# Battery_Charger.net
KiCad netlist of a schematic drawn in Altium Designer
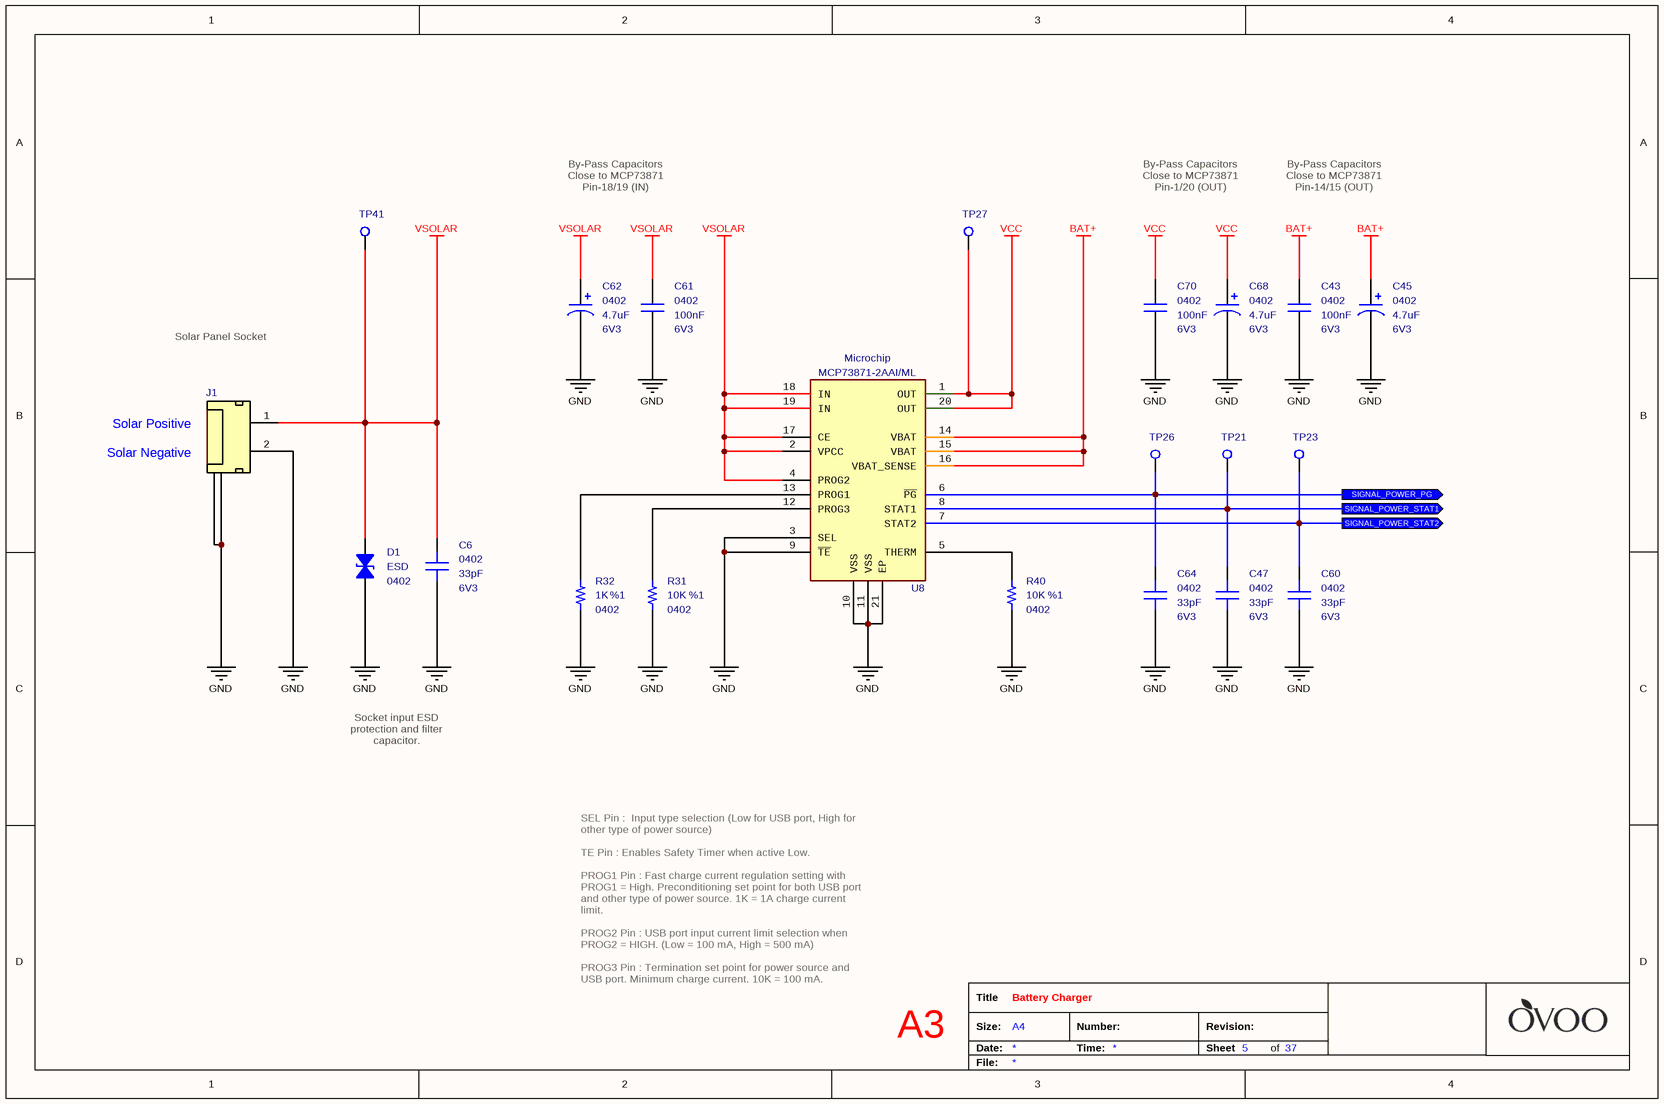
[diagram p0: Battery Charger.SchDoc]

(export (version "E")
  (design (tool "Eeschema 10.0.6"))
  (components
    (comp (ref "C6")
      (value "33pF")
      (footprint "CAPACITOR_0402")
      (description "Capacitor - 33pF [0402] (Ceramic)")
      (fields
        (field (name "MANUFACTURER_PART_NUMBER") "C0402C330J9RACAUTO")
        (field (name "MOUSER_PART_NUMBER") "80-C0402C330J9RAUTO")
        (field (name "CASE") "0402")
        (field (name "VOLTAGE") "6V3")
      )
      (libsource (lib "Ovoo_Schematic") (part "Capacitor - 33pF [0402-6V3]"))
    )
    (comp (ref "C43")
      (value "100nF")
      (footprint "CAPACITOR_0402")
      (description "Capacitor - 100nF [0402-6V3] (Ceramic)")
      (fields
        (field (name "MANUFACTURER_PART_NUMBER") "04026D104KAT4A")
        (field (name "MOUSER_PART_NUMBER") "581-04026D104KAT4A")
        (field (name "CASE") "0402")
        (field (name "VOLTAGE") "6V3")
      )
      (libsource (lib "Ovoo_Schematic") (part "Capacitor - 100nF [0402-6V3]"))
    )
    (comp (ref "C45")
      (value "4.7uF")
      (footprint "CAPACITOR_0402")
      (description "Capacitor - 4.7uF [0402] (Ceramic)")
      (fields
        (field (name "MANUFACTURER_PART_NUMBER") "C0402C475M9PACTU")
        (field (name "MOUSER_PART_NUMBER") "80-C0402C475M9P")
        (field (name "CASE") "0402")
        (field (name "VOLTAGE") "6V3")
      )
      (libsource (lib "Ovoo_Schematic") (part "Capacitor - 4.7uF [0402-6V3)"))
    )
    (comp (ref "C47")
      (value "33pF")
      (footprint "CAPACITOR_0402")
      (description "Capacitor - 33pF [0402] (Ceramic)")
      (fields
        (field (name "MANUFACTURER_PART_NUMBER") "C0402C330J9RACAUTO")
        (field (name "MOUSER_PART_NUMBER") "80-C0402C330J9RAUTO")
        (field (name "CASE") "0402")
        (field (name "VOLTAGE") "6V3")
      )
      (libsource (lib "Ovoo_Schematic") (part "Capacitor - 33pF [0402-6V3]"))
    )
    (comp (ref "C60")
      (value "33pF")
      (footprint "CAPACITOR_0402")
      (description "Capacitor - 33pF [0402] (Ceramic)")
      (fields
        (field (name "MANUFACTURER_PART_NUMBER") "C0402C330J9RACAUTO")
        (field (name "MOUSER_PART_NUMBER") "80-C0402C330J9RAUTO")
        (field (name "CASE") "0402")
        (field (name "VOLTAGE") "6V3")
      )
      (libsource (lib "Ovoo_Schematic") (part "Capacitor - 33pF [0402-6V3]"))
    )
    (comp (ref "C61")
      (value "100nF")
      (footprint "CAPACITOR_0402")
      (description "Capacitor - 100nF [0402-6V3] (Ceramic)")
      (fields
        (field (name "MANUFACTURER_PART_NUMBER") "04026D104KAT4A")
        (field (name "MOUSER_PART_NUMBER") "581-04026D104KAT4A")
        (field (name "CASE") "0402")
        (field (name "VOLTAGE") "6V3")
      )
      (libsource (lib "Ovoo_Schematic") (part "Capacitor - 100nF [0402-6V3]"))
    )
    (comp (ref "C62")
      (value "4.7uF")
      (footprint "CAPACITOR_0402")
      (description "Capacitor - 4.7uF [0402] (Ceramic)")
      (fields
        (field (name "MANUFACTURER_PART_NUMBER") "C0402C475M9PACTU")
        (field (name "MOUSER_PART_NUMBER") "80-C0402C475M9P")
        (field (name "CASE") "0402")
        (field (name "VOLTAGE") "6V3")
      )
      (libsource (lib "Ovoo_Schematic") (part "Capacitor - 4.7uF [0402-6V3)"))
    )
    (comp (ref "C64")
      (value "33pF")
      (footprint "CAPACITOR_0402")
      (description "Capacitor - 33pF [0402] (Ceramic)")
      (fields
        (field (name "MANUFACTURER_PART_NUMBER") "C0402C330J9RACAUTO")
        (field (name "MOUSER_PART_NUMBER") "80-C0402C330J9RAUTO")
        (field (name "CASE") "0402")
        (field (name "VOLTAGE") "6V3")
      )
      (libsource (lib "Ovoo_Schematic") (part "Capacitor - 33pF [0402-6V3]"))
    )
    (comp (ref "C68")
      (value "4.7uF")
      (footprint "CAPACITOR_0402")
      (description "Capacitor - 4.7uF [0402] (Ceramic)")
      (fields
        (field (name "MANUFACTURER_PART_NUMBER") "C0402C475M9PACTU")
        (field (name "MOUSER_PART_NUMBER") "80-C0402C475M9P")
        (field (name "CASE") "0402")
        (field (name "VOLTAGE") "6V3")
      )
      (libsource (lib "Ovoo_Schematic") (part "Capacitor - 4.7uF [0402-6V3)"))
    )
    (comp (ref "C70")
      (value "100nF")
      (footprint "CAPACITOR_0402")
      (description "Capacitor - 100nF [0402-6V3] (Ceramic)")
      (fields
        (field (name "MANUFACTURER_PART_NUMBER") "04026D104KAT4A")
        (field (name "MOUSER_PART_NUMBER") "581-04026D104KAT4A")
        (field (name "CASE") "0402")
        (field (name "VOLTAGE") "6V3")
      )
      (libsource (lib "Ovoo_Schematic") (part "Capacitor - 100nF [0402-6V3]"))
    )
    (comp (ref "D1")
      (value "ESD Suppressors")
      (footprint "ESD_0402")
      (description "TVS Diode (Bi-directional)")
      (fields
        (field (name "MANUFACTURER_PART_NUMBER") "0402ESDA-MLP1")
        (field (name "MOUSER_PART_NUMBER") "504-0402ESDA-MLP1")
        (field (name "CASE") "0402")
      )
      (libsource (lib "Ovoo_Schematic") (part "Diode - ESD Protection"))
    )
    (comp (ref "J1")
      (value "Solar Power Socket")
      (footprint "Connector_Tunic 2P - H")
      (description "Mini Tunic Connector with 2P")
      (fields
        (field (name "MANUFACTURER_PART_NUMBER") "53261-0271")
        (field (name "MOUSER_PART_NUMBER") "538-53261-0271")
      )
      (libsource (lib "Ovoo_Schematic") (part "Connector - Mini Tunic 2P (1.25)"))
    )
    (comp (ref "R31")
      (value "10K")
      (footprint "RESISTOR_0402")
      (description "Thick Film Resistors - SMD 1/16 W 10 Kohms 1%")
      (fields
        (field (name "MANUFACTURER_PART_NUMBER") "CRCW040210K0FKED")
        (field (name "MOUSER_PART_NUMBER") "71-CRCW0402-10K-E3")
        (field (name "TOLERANCE") "%1")
        (field (name "CASE") "0402")
      )
      (libsource (lib "Ovoo_Schematic") (part "Resistor - 10K"))
    )
    (comp (ref "R32")
      (value "1K")
      (footprint "RESISTOR_0402")
      (description "Thick Film Resistors - SMD 1/16 W 1.0 Kohms 1%")
      (fields
        (field (name "MANUFACTURER_PART_NUMBER") "CRCW04021K00FKED")
        (field (name "MOUSER_PART_NUMBER") "71-CRCW0402-1.0K-E3")
        (field (name "CASE") "0402")
        (field (name "TOLERANCE") "%1")
      )
      (libsource (lib "Ovoo_Schematic") (part "Resistor - 1K"))
    )
    (comp (ref "R40")
      (value "10K")
      (footprint "RESISTOR_0402")
      (description "Thick Film Resistors - SMD 1/16 W 10 Kohms 1%")
      (fields
        (field (name "MANUFACTURER_PART_NUMBER") "CRCW040210K0FKED")
        (field (name "MOUSER_PART_NUMBER") "71-CRCW0402-10K-E3")
        (field (name "TOLERANCE") "%1")
        (field (name "CASE") "0402")
      )
      (libsource (lib "Ovoo_Schematic") (part "Resistor - 10K"))
    )
    (comp (ref "TP21")
      (value "PCB - Test Point")
      (footprint "Test_Pad - Hole")
      (description "Test Point")
      (libsource (lib "Ovoo_Schematic") (part "PCB - Test Point"))
    )
    (comp (ref "TP23")
      (value "PCB - Test Point")
      (footprint "Test_Pad - Hole")
      (description "Test Point")
      (libsource (lib "Ovoo_Schematic") (part "PCB - Test Point"))
    )
    (comp (ref "TP26")
      (value "PCB - Test Point")
      (footprint "Test_Pad - Hole")
      (description "Test Point")
      (libsource (lib "Ovoo_Schematic") (part "PCB - Test Point"))
    )
    (comp (ref "TP27")
      (value "PCB - Test Point")
      (footprint "Test_Pad - Hole")
      (description "Test Point")
      (libsource (lib "Ovoo_Schematic") (part "PCB - Test Point"))
    )
    (comp (ref "TP41")
      (value "PCB - Test Point")
      (footprint "Test_Pad - Hole")
      (description "Test Point")
      (libsource (lib "Ovoo_Schematic") (part "PCB - Test Point"))
    )
    (comp (ref "U8")
      (value "Battery Charger")
      (footprint "QFN20")
      (description "Battery Management USB/AC Battery Charger")
      (fields
        (field (name "MANUFACTURER_NAME") "Microchip")
        (field (name "MANUFACTURER_PART_NUMBER") "MCP73871-2AAI/ML")
        (field (name "MOUSER_PART_NUMBER") "579-MCP73871-2AAI/ML")
      )
      (libsource (lib "Ovoo_Schematic") (part "IC - MCP73871"))
    )
  )
  (nets
    (net (code "1") (name "/SIGNAL_POWER_PG") (class "Default")
      (node (ref "C64") (pin "1") (pinfunction "1_1") (pintype "passive"))
      (node (ref "TP26") (pin "1") (pinfunction "1_1") (pintype "passive"))
      (node (ref "U8") (pin "6") (pinfunction "~{PG}_6") (pintype "open_collector"))
    )
    (net (code "2") (name "/SIGNAL_POWER_STAT1") (class "Default")
      (node (ref "C47") (pin "1") (pinfunction "1_1") (pintype "passive"))
      (node (ref "TP21") (pin "1") (pinfunction "1_1") (pintype "passive"))
      (node (ref "U8") (pin "8") (pinfunction "STAT1_8") (pintype "open_collector"))
    )
    (net (code "3") (name "/SIGNAL_POWER_STAT2") (class "Default")
      (node (ref "C60") (pin "1") (pinfunction "1_1") (pintype "passive"))
      (node (ref "TP23") (pin "1") (pinfunction "1_1") (pintype "passive"))
      (node (ref "U8") (pin "7") (pinfunction "STAT2_7") (pintype "open_collector"))
    )
    (net (code "4") (name "BAT+") (class "Default")
      (node (ref "C43") (pin "1") (pinfunction "1_1") (pintype "passive"))
      (node (ref "C45") (pin "1") (pinfunction "1_1") (pintype "passive"))
      (node (ref "U8") (pin "14") (pinfunction "VBAT_14") (pintype "power_in"))
      (node (ref "U8") (pin "15") (pinfunction "VBAT_15") (pintype "power_in"))
      (node (ref "U8") (pin "16") (pinfunction "VBAT_SENSE_16") (pintype "power_in"))
    )
    (net (code "5") (name "GND") (class "Default")
      (node (ref "C43") (pin "2") (pinfunction "2_2") (pintype "passive"))
      (node (ref "C45") (pin "2") (pinfunction "2_2") (pintype "passive"))
      (node (ref "C47") (pin "2") (pinfunction "2_2") (pintype "passive"))
      (node (ref "C6") (pin "1") (pinfunction "1_1") (pintype "passive"))
      (node (ref "C60") (pin "2") (pinfunction "2_2") (pintype "passive"))
      (node (ref "C61") (pin "2") (pinfunction "2_2") (pintype "passive"))
      (node (ref "C62") (pin "2") (pinfunction "2_2") (pintype "passive"))
      (node (ref "C64") (pin "2") (pinfunction "2_2") (pintype "passive"))
      (node (ref "C68") (pin "2") (pinfunction "2_2") (pintype "passive"))
      (node (ref "C70") (pin "2") (pinfunction "2_2") (pintype "passive"))
      (node (ref "D1") (pin "1") (pinfunction "1_1") (pintype "passive"))
      (node (ref "J1") (pin "2") (pinfunction "GND_2") (pintype "power_in"))
      (node (ref "J1") (pin "3") (pinfunction "Termination_3") (pintype "passive"))
      (node (ref "J1") (pin "4") (pinfunction "Termination_4") (pintype "passive"))
      (node (ref "R31") (pin "1") (pinfunction "1_1") (pintype "passive"))
      (node (ref "R32") (pin "1") (pinfunction "1_1") (pintype "passive"))
      (node (ref "R40") (pin "1") (pinfunction "1_1") (pintype "passive"))
      (node (ref "U8") (pin "10") (pinfunction "VSS_10") (pintype "power_in"))
      (node (ref "U8") (pin "11") (pinfunction "VSS_11") (pintype "power_in"))
      (node (ref "U8") (pin "21") (pinfunction "EP_21") (pintype "passive"))
      (node (ref "U8") (pin "3") (pinfunction "SEL_3") (pintype "passive"))
      (node (ref "U8") (pin "9") (pinfunction "~{TE}_9") (pintype "passive"))
    )
    (net (code "6") (name "Net-(U8-PROG1)") (class "Default")
      (node (ref "R32") (pin "2") (pinfunction "2_2") (pintype "passive"))
      (node (ref "U8") (pin "13") (pinfunction "PROG1_13") (pintype "passive"))
    )
    (net (code "7") (name "Net-(U8-PROG3)") (class "Default")
      (node (ref "R31") (pin "2") (pinfunction "2_2") (pintype "passive"))
      (node (ref "U8") (pin "12") (pinfunction "PROG3_12") (pintype "passive"))
    )
    (net (code "8") (name "Net-(U8-THERM)") (class "Default")
      (node (ref "R40") (pin "2") (pinfunction "2_2") (pintype "passive"))
      (node (ref "U8") (pin "5") (pinfunction "THERM_5") (pintype "passive"))
    )
    (net (code "9") (name "VCC") (class "Default")
      (node (ref "C68") (pin "1") (pinfunction "1_1") (pintype "passive"))
      (node (ref "C70") (pin "1") (pinfunction "1_1") (pintype "passive"))
      (node (ref "TP27") (pin "1") (pinfunction "1_1") (pintype "passive"))
      (node (ref "U8") (pin "1") (pinfunction "OUT_1") (pintype "power_in"))
      (node (ref "U8") (pin "20") (pinfunction "OUT_20") (pintype "power_in"))
    )
    (net (code "10") (name "VSOLAR") (class "Default")
      (node (ref "C6") (pin "2") (pinfunction "2_2") (pintype "passive"))
      (node (ref "C61") (pin "1") (pinfunction "1_1") (pintype "passive"))
      (node (ref "C62") (pin "1") (pinfunction "1_1") (pintype "passive"))
      (node (ref "D1") (pin "2") (pinfunction "2_2") (pintype "passive"))
      (node (ref "J1") (pin "1") (pinfunction "VSolar_1") (pintype "power_in"))
      (node (ref "TP41") (pin "1") (pinfunction "1_1") (pintype "passive"))
      (node (ref "U8") (pin "17") (pinfunction "CE_17") (pintype "passive"))
      (node (ref "U8") (pin "18") (pinfunction "IN_18") (pintype "power_in"))
      (node (ref "U8") (pin "19") (pinfunction "IN_19") (pintype "power_in"))
      (node (ref "U8") (pin "2") (pinfunction "VPCC_2") (pintype "passive"))
      (node (ref "U8") (pin "4") (pinfunction "PROG2_4") (pintype "passive"))
    )
  )
)
